# Schaltplan_Eagle-Format.net
KiCad netlist of a schematic drawn in EAGLE
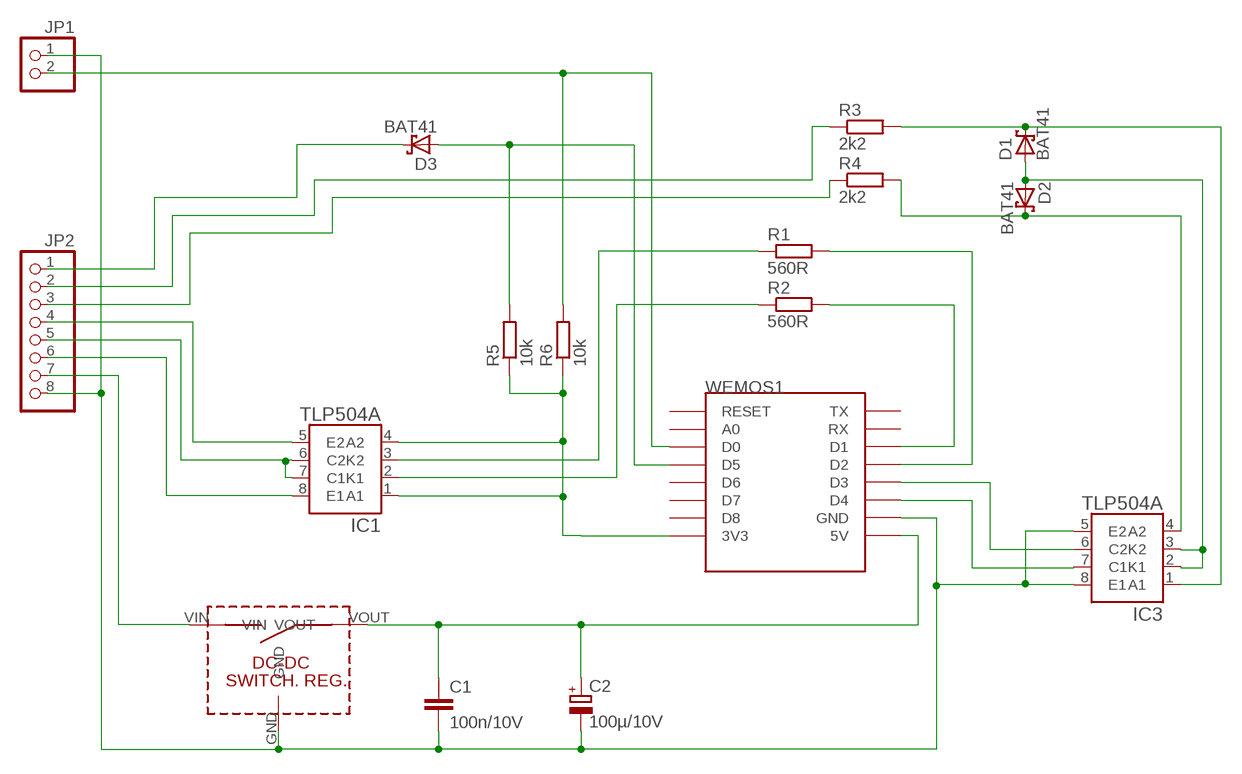
[diagram p0: schematic, sheet 1]

(export (version "E")
  (design (tool "Eeschema 10.0.6"))
  (components
    (comp (ref "C1")
      (value "100n/10V")
      (footprint "eagle-import:C2.5-2")
      (libsource (lib "eagle-import") (part "C2.5/2"))
    )
    (comp (ref "C2")
      (value "100µ/10V")
      (footprint "eagle-import:E2,5-6")
      (libsource (lib "eagle-import") (part "CPOL-EUE2.5-6"))
    )
    (comp (ref "D1")
      (value "BAT41")
      (footprint "eagle-import:DO35-7")
      (fields (field (name "SPICEPREFIX") "D"))
      (libsource (lib "eagle-import") (part "SCHOTTKY-DIODEDO35-7"))
    )
    (comp (ref "D2")
      (value "BAT41")
      (footprint "eagle-import:DO35-7")
      (fields (field (name "SPICEPREFIX") "D"))
      (libsource (lib "eagle-import") (part "SCHOTTKY-DIODEDO35-7"))
    )
    (comp (ref "D3")
      (value "BAT41")
      (footprint "eagle-import:DO35-7")
      (fields (field (name "SPICEPREFIX") "D"))
      (libsource (lib "eagle-import") (part "SCHOTTKY-DIODEDO35-7"))
    )
    (comp (ref "IC1")
      (value "TLP504A")
      (footprint "eagle-import:DIL8_2")
      (libsource (lib "eagle-import") (part "TLP504A_2"))
    )
    (comp (ref "IC3")
      (value "TLP504A")
      (footprint "eagle-import:DIL8_2")
      (libsource (lib "eagle-import") (part "TLP504A_2"))
    )
    (comp (ref "JP1")
      (value "PINHD-1X2")
      (footprint "eagle-import:1X02")
      (libsource (lib "eagle-import") (part "PINHD-1X2"))
    )
    (comp (ref "JP2")
      (value "PINHD-1X8")
      (footprint "eagle-import:1X08")
      (libsource (lib "eagle-import") (part "PINHD-1X8"))
    )
    (comp (ref "R1")
      (value "560R")
      (footprint "eagle-import:0204_5")
      (libsource (lib "eagle-import") (part "R-EU_0204/5"))
    )
    (comp (ref "R2")
      (value "560R")
      (footprint "eagle-import:0204_5")
      (libsource (lib "eagle-import") (part "R-EU_0204/5"))
    )
    (comp (ref "R3")
      (value "2k2")
      (footprint "eagle-import:0204_5")
      (libsource (lib "eagle-import") (part "R-EU_0204/5"))
    )
    (comp (ref "R4")
      (value "2k2")
      (footprint "eagle-import:0204_5")
      (libsource (lib "eagle-import") (part "R-EU_0204/5"))
    )
    (comp (ref "R5")
      (value "10k")
      (footprint "eagle-import:0204_5")
      (libsource (lib "eagle-import") (part "R-EU_0204/5"))
    )
    (comp (ref "R6")
      (value "10k")
      (footprint "eagle-import:0204_5")
      (libsource (lib "eagle-import") (part "R-EU_0204/5"))
    )
    (comp (ref "R78E5.0-0.5")
      (value "R-78E5.0-0.5")
      (footprint "eagle-import:R-78E5")
      (fields (field (name "SPICEPREFIX") "X"))
      (libsource (lib "eagle-import") (part "R-78ER-78E5"))
    )
    (comp (ref "WEMOS1")
      (value "WEMOS-D1-MINI")
      (footprint "eagle-import:WEMOS-D1-MINI")
      (libsource (lib "eagle-import") (part "WEMOS-D1-MINI"))
    )
  )
  (nets
    (net (code "1") (name "Net-(C1-Pad1)") (class "Default")
      (node (ref "C1") (pin "1") (pinfunction "1_1") (pintype "passive"))
      (node (ref "C2") (pin "+") (pinfunction "+_+") (pintype "passive"))
      (node (ref "R78E5.0-0.5") (pin "VOUT") (pinfunction "VOUT_VOUT") (pintype "power_in"))
      (node (ref "WEMOS1") (pin "5V") (pinfunction "5V_5V") (pintype "bidirectional"))
    )
    (net (code "2") (name "Net-(D3-PadA)") (class "Default")
      (node (ref "D3") (pin "A") (pinfunction "A_A") (pintype "passive"))
      (node (ref "R5") (pin "2") (pinfunction "2_2") (pintype "passive"))
      (node (ref "WEMOS1") (pin "D5") (pinfunction "D5_D5") (pintype "bidirectional"))
    )
    (net (code "3") (name "Net-(D3-PadC)") (class "Default")
      (node (ref "D3") (pin "C") (pinfunction "C_C") (pintype "passive"))
      (node (ref "JP2") (pin "1") (pinfunction "1_1") (pintype "passive"))
    )
    (net (code "4") (name "Net-(IC1-A1)") (class "Default")
      (node (ref "IC1") (pin "1") (pinfunction "A1_1") (pintype "passive"))
      (node (ref "IC1") (pin "4") (pinfunction "A2_4") (pintype "passive"))
      (node (ref "R5") (pin "1") (pinfunction "1_1") (pintype "passive"))
      (node (ref "R6") (pin "1") (pinfunction "1_1") (pintype "passive"))
      (node (ref "WEMOS1") (pin "3V3") (pinfunction "3V3_3V3") (pintype "bidirectional"))
    )
    (net (code "5") (name "Net-(IC1-C2)") (class "Default")
      (node (ref "IC1") (pin "6") (pinfunction "C2_6") (pintype "passive"))
      (node (ref "JP2") (pin "5") (pinfunction "5_5") (pintype "passive"))
    )
    (net (code "6") (name "Net-(IC1-E1)") (class "Default")
      (node (ref "IC1") (pin "8") (pinfunction "E1_8") (pintype "passive"))
      (node (ref "JP2") (pin "6") (pinfunction "6_6") (pintype "passive"))
    )
    (net (code "7") (name "Net-(IC1-E2)") (class "Default")
      (node (ref "IC1") (pin "5") (pinfunction "E2_5") (pintype "passive"))
      (node (ref "JP2") (pin "4") (pinfunction "4_4") (pintype "passive"))
    )
    (net (code "8") (name "Net-(IC1-K1)") (class "Default")
      (node (ref "IC1") (pin "2") (pinfunction "K1_2") (pintype "passive"))
      (node (ref "R2") (pin "1") (pinfunction "1_1") (pintype "passive"))
    )
    (net (code "9") (name "Net-(IC1-K2)") (class "Default")
      (node (ref "IC1") (pin "3") (pinfunction "K2_3") (pintype "passive"))
      (node (ref "R1") (pin "1") (pinfunction "1_1") (pintype "passive"))
    )
    (net (code "10") (name "Net-(IC3-A1)") (class "Default")
      (node (ref "D1") (pin "C") (pinfunction "C_C") (pintype "passive"))
      (node (ref "IC3") (pin "1") (pinfunction "A1_1") (pintype "passive"))
      (node (ref "R3") (pin "2") (pinfunction "2_2") (pintype "passive"))
    )
    (net (code "11") (name "Net-(IC3-A2)") (class "Default")
      (node (ref "D2") (pin "C") (pinfunction "C_C") (pintype "passive"))
      (node (ref "IC3") (pin "4") (pinfunction "A2_4") (pintype "passive"))
      (node (ref "R4") (pin "2") (pinfunction "2_2") (pintype "passive"))
    )
    (net (code "12") (name "Net-(IC3-C1)") (class "Default")
      (node (ref "IC3") (pin "7") (pinfunction "C1_7") (pintype "passive"))
      (node (ref "WEMOS1") (pin "D4") (pinfunction "D4_D4") (pintype "bidirectional"))
    )
    (net (code "13") (name "Net-(IC3-C2)") (class "Default")
      (node (ref "IC3") (pin "6") (pinfunction "C2_6") (pintype "passive"))
      (node (ref "WEMOS1") (pin "D3") (pinfunction "D3_D3") (pintype "bidirectional"))
    )
    (net (code "14") (name "Net-(IC3-E1)") (class "Default")
      (node (ref "C1") (pin "2") (pinfunction "2_2") (pintype "passive"))
      (node (ref "C2") (pin "-") (pinfunction "-_-") (pintype "passive"))
      (node (ref "IC3") (pin "8") (pinfunction "E1_8") (pintype "passive"))
      (node (ref "JP1") (pin "1") (pinfunction "1_1") (pintype "passive"))
      (node (ref "JP2") (pin "8") (pinfunction "8_8") (pintype "passive"))
      (node (ref "R78E5.0-0.5") (pin "GND") (pinfunction "GND_GND") (pintype "power_in"))
      (node (ref "WEMOS1") (pin "GND") (pinfunction "GND_GND") (pintype "bidirectional"))
    )
    (net (code "15") (name "Net-(IC3-K1)") (class "Default")
      (node (ref "D1") (pin "A") (pinfunction "A_A") (pintype "passive"))
      (node (ref "D2") (pin "A") (pinfunction "A_A") (pintype "passive"))
      (node (ref "IC3") (pin "2") (pinfunction "K1_2") (pintype "passive"))
      (node (ref "IC3") (pin "3") (pinfunction "K2_3") (pintype "passive"))
    )
    (net (code "16") (name "Net-(JP1-Pad2)") (class "Default")
      (node (ref "JP1") (pin "2") (pinfunction "2_2") (pintype "passive"))
      (node (ref "R6") (pin "2") (pinfunction "2_2") (pintype "passive"))
      (node (ref "WEMOS1") (pin "D0") (pinfunction "D0_D0") (pintype "bidirectional"))
    )
    (net (code "17") (name "Net-(JP2-Pad2)") (class "Default")
      (node (ref "JP2") (pin "2") (pinfunction "2_2") (pintype "passive"))
      (node (ref "R3") (pin "1") (pinfunction "1_1") (pintype "passive"))
    )
    (net (code "18") (name "Net-(JP2-Pad3)") (class "Default")
      (node (ref "JP2") (pin "3") (pinfunction "3_3") (pintype "passive"))
      (node (ref "R4") (pin "1") (pinfunction "1_1") (pintype "passive"))
    )
    (net (code "19") (name "Net-(JP2-Pad7)") (class "Default")
      (node (ref "JP2") (pin "7") (pinfunction "7_7") (pintype "passive"))
      (node (ref "R78E5.0-0.5") (pin "VIN") (pinfunction "VIN_VIN") (pintype "power_in"))
    )
    (net (code "20") (name "Net-(R1-Pad2)") (class "Default")
      (node (ref "R1") (pin "2") (pinfunction "2_2") (pintype "passive"))
      (node (ref "WEMOS1") (pin "D2") (pinfunction "D2_D2") (pintype "bidirectional"))
    )
    (net (code "21") (name "Net-(R2-Pad2)") (class "Default")
      (node (ref "R2") (pin "2") (pinfunction "2_2") (pintype "passive"))
      (node (ref "WEMOS1") (pin "D1") (pinfunction "D1_D1") (pintype "bidirectional"))
    )
    (net (code "22") (name "unconnected-(IC1-C1-Pad7)") (class "Default")
      (node (ref "IC1") (pin "7") (pinfunction "C1_7") (pintype "passive"))
    )
    (net (code "23") (name "unconnected-(IC3-E2-Pad5)") (class "Default")
      (node (ref "IC3") (pin "5") (pinfunction "E2_5") (pintype "passive"))
    )
    (net (code "24") (name "unconnected-(WEMOS1-PadA0)") (class "Default")
      (node (ref "WEMOS1") (pin "A0") (pinfunction "A0_A0") (pintype "bidirectional"))
    )
    (net (code "25") (name "unconnected-(WEMOS1-PadD6)") (class "Default")
      (node (ref "WEMOS1") (pin "D6") (pinfunction "D6_D6") (pintype "bidirectional"))
    )
    (net (code "26") (name "unconnected-(WEMOS1-PadD7)") (class "Default")
      (node (ref "WEMOS1") (pin "D7") (pinfunction "D7_D7") (pintype "bidirectional"))
    )
    (net (code "27") (name "unconnected-(WEMOS1-PadD8)") (class "Default")
      (node (ref "WEMOS1") (pin "D8") (pinfunction "D8_D8") (pintype "bidirectional"))
    )
    (net (code "28") (name "unconnected-(WEMOS1-PadRESET)") (class "Default")
      (node (ref "WEMOS1") (pin "RESET") (pinfunction "RESET_RESET") (pintype "bidirectional"))
    )
    (net (code "29") (name "unconnected-(WEMOS1-PadRX)") (class "Default")
      (node (ref "WEMOS1") (pin "RX") (pinfunction "RX_RX") (pintype "bidirectional"))
    )
    (net (code "30") (name "unconnected-(WEMOS1-PadTX)") (class "Default")
      (node (ref "WEMOS1") (pin "TX") (pinfunction "TX_TX") (pintype "bidirectional"))
    )
  )
)
